# interface_com_usuario_comunicacao.net
KiCad netlist of a schematic drawn in Altium Designer
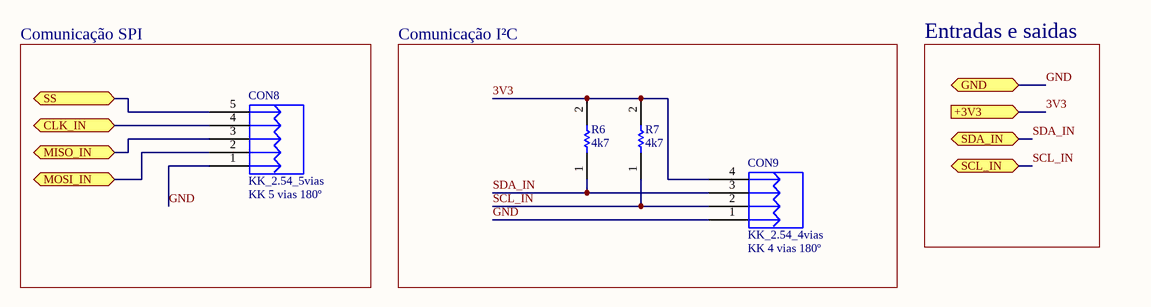
[diagram p0: interface_com_usuario_comunicacao.SchDoc]

(export (version "E")
  (design (tool "Eeschema 10.0.6"))
  (components
    (comp (ref "CON8")
      (value "KK_2.54_5vias")
      (footprint "KK_5vias_180°")
      (description "Conector KK 2.54mm 5 vias")
      (fields (field (name "VALOR") "KK 5 vias 180º"))
      (libsource (lib "Sinaliza玢o_Official") (part "KK_2.54_5vias"))
    )
    (comp (ref "CON9")
      (value "KK_2.54_4vias")
      (footprint "KK_4vias_180°")
      (description "Conector KK 2.54mm 4 vias")
      (fields (field (name "VALOR") "KK 4 vias 180º"))
      (libsource (lib "Sinaliza玢o_Official") (part "KK_2.54_4vias"))
    )
    (comp (ref "R6")
      (value "4k7")
      (footprint "RESC3216X60N")
      (description "RES 1206 5%")
      (fields
        (field (name "MANUFACTURER_PART_NUMBER") "CRCW12064K70FKEA")
        (field (name "MOUSER PART NUMBER") "71-CRCW1206-4.7K-E3")
      )
      (libsource (lib "RoboHospitalar") (part "RES 1206"))
    )
    (comp (ref "R7")
      (value "4k7")
      (footprint "RESC3216X60N")
      (description "RES 1206 5%")
      (fields
        (field (name "MANUFACTURER_PART_NUMBER") "CRCW12064K70FKEA")
        (field (name "MOUSER PART NUMBER") "71-CRCW1206-4.7K-E3")
      )
      (libsource (lib "RoboHospitalar") (part "RES 1206"))
    )
  )
  (nets
    (net (code "1") (name "/3V3") (class "Default")
      (node (ref "CON9") (pin "4") (pintype "passive"))
      (node (ref "R6") (pin "2") (pinfunction "2_2") (pintype "passive"))
      (node (ref "R7") (pin "2") (pinfunction "2_2") (pintype "passive"))
    )
    (net (code "2") (name "/CLK_IN") (class "Default") (node (ref "CON8") (pin "4") (pintype "passive")))
    (net (code "3") (name "/GND") (class "Default")
      (node (ref "CON8") (pin "1") (pintype "passive"))
      (node (ref "CON9") (pin "1") (pintype "passive"))
    )
    (net (code "4") (name "/MISO_IN") (class "Default") (node (ref "CON8") (pin "3") (pintype "passive")))
    (net (code "5") (name "/MOSI_IN") (class "Default") (node (ref "CON8") (pin "2") (pintype "passive")))
    (net (code "6") (name "/SCL_IN") (class "Default")
      (node (ref "CON9") (pin "2") (pintype "passive"))
      (node (ref "R7") (pin "1") (pinfunction "1_1") (pintype "passive"))
    )
    (net (code "7") (name "/SDA_IN") (class "Default")
      (node (ref "CON9") (pin "3") (pintype "passive"))
      (node (ref "R6") (pin "1") (pinfunction "1_1") (pintype "passive"))
    )
    (net (code "8") (name "/SS") (class "Default") (node (ref "CON8") (pin "5") (pintype "passive")))
  )
)
